# Converter.net
KiCad netlist of a schematic drawn in Altium Designer
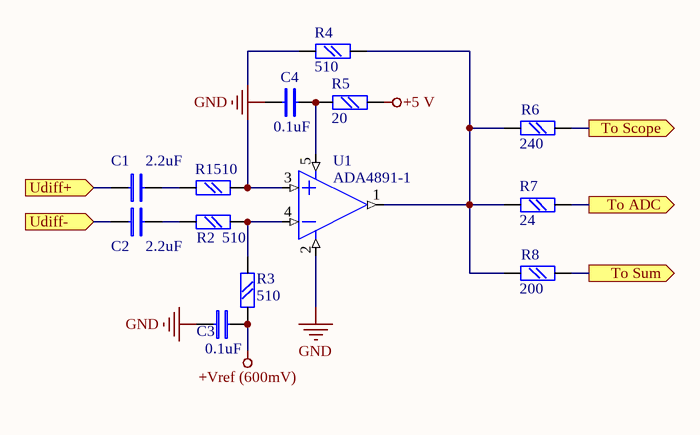
[diagram p0: Converter.SchDoc]

(export (version "E")
  (design (tool "Eeschema 10.0.6"))
  (components
    (comp (ref "C1") (value "2.2uF") (footprint "chip0603") (libsource (lib "vDevice") (part "C")))
    (comp (ref "C2") (value "2.2uF") (footprint "chip0603") (libsource (lib "vDevice") (part "C")))
    (comp (ref "C3") (value "0.1uF") (footprint "chip0603") (libsource (lib "vDevice") (part "C")))
    (comp (ref "C4") (value "0.1uF") (footprint "chip0603") (libsource (lib "vDevice") (part "C")))
    (comp (ref "R1") (value "510") (footprint "chip0603") (libsource (lib "vDevice") (part "R")))
    (comp (ref "R2") (value "510") (footprint "chip0603") (libsource (lib "vDevice") (part "R")))
    (comp (ref "R3") (value "510") (footprint "chip0603") (libsource (lib "vDevice") (part "R")))
    (comp (ref "R4") (value "510") (footprint "chip0603") (libsource (lib "vDevice") (part "R")))
    (comp (ref "R5") (value "20") (footprint "chip0603") (libsource (lib "vDevice") (part "R")))
    (comp (ref "R6") (value "240") (footprint "chip0603") (libsource (lib "vDevice") (part "R")))
    (comp (ref "R7") (value "24") (footprint "chip0603") (libsource (lib "vDevice") (part "R")))
    (comp (ref "R8") (value "200") (footprint "chip0603") (libsource (lib "vDevice") (part "R")))
    (comp (ref "U1") (value "ADA4891-1") (footprint "SOT23-5") (libsource (lib "vAnalog") (part "AD8005ART")))
  )
  (nets
    (net (code "1") (name "+5 V") (class "Default")
      (node (ref "R5") (pin "1") (pinfunction "1_1") (pintype "passive"))
    )
    (net (code "2") (name "+Vref (600mV)") (class "Default")
      (node (ref "C3") (pin "2") (pinfunction "2_2") (pintype "passive"))
      (node (ref "R3") (pin "2") (pinfunction "2_2") (pintype "passive"))
    )
    (net (code "3") (name "/To ADC") (class "Default")
      (node (ref "R7") (pin "2") (pinfunction "2_2") (pintype "passive"))
    )
    (net (code "4") (name "/To Scope") (class "Default")
      (node (ref "R6") (pin "2") (pinfunction "2_2") (pintype "passive"))
    )
    (net (code "5") (name "/To Sum") (class "Default")
      (node (ref "R8") (pin "2") (pinfunction "2_2") (pintype "passive"))
    )
    (net (code "6") (name "/Udiff+") (class "Default")
      (node (ref "C1") (pin "1") (pinfunction "1_1") (pintype "passive"))
    )
    (net (code "7") (name "/Udiff-") (class "Default")
      (node (ref "C2") (pin "1") (pinfunction "1_1") (pintype "passive"))
    )
    (net (code "8") (name "GND") (class "Default")
      (node (ref "C3") (pin "1") (pinfunction "1_1") (pintype "passive"))
      (node (ref "C4") (pin "1") (pinfunction "1_1") (pintype "passive"))
      (node (ref "U1") (pin "2") (pinfunction "E-_2") (pintype "input"))
    )
    (net (code "9") (name "Net-(C1-Pad2)") (class "Default")
      (node (ref "C1") (pin "2") (pinfunction "2_2") (pintype "passive"))
      (node (ref "R1") (pin "1") (pinfunction "1_1") (pintype "passive"))
    )
    (net (code "10") (name "Net-(C2-Pad2)") (class "Default")
      (node (ref "C2") (pin "2") (pinfunction "2_2") (pintype "passive"))
      (node (ref "R2") (pin "1") (pinfunction "1_1") (pintype "passive"))
    )
    (net (code "11") (name "Net-(U1-+IN)") (class "Default")
      (node (ref "R1") (pin "2") (pinfunction "2_2") (pintype "passive"))
      (node (ref "R4") (pin "1") (pinfunction "1_1") (pintype "passive"))
      (node (ref "U1") (pin "3") (pinfunction "+IN_3") (pintype "input"))
    )
    (net (code "12") (name "Net-(U1--IN)") (class "Default")
      (node (ref "R2") (pin "2") (pinfunction "2_2") (pintype "passive"))
      (node (ref "R3") (pin "1") (pinfunction "1_1") (pintype "passive"))
      (node (ref "U1") (pin "4") (pinfunction "-IN_4") (pintype "input"))
    )
    (net (code "13") (name "Net-(U1-E+)") (class "Default")
      (node (ref "C4") (pin "2") (pinfunction "2_2") (pintype "passive"))
      (node (ref "R5") (pin "2") (pinfunction "2_2") (pintype "passive"))
      (node (ref "U1") (pin "5") (pinfunction "E+_5") (pintype "input"))
    )
    (net (code "14") (name "Net-(U1-OUT)") (class "Default")
      (node (ref "R4") (pin "2") (pinfunction "2_2") (pintype "passive"))
      (node (ref "R6") (pin "1") (pinfunction "1_1") (pintype "passive"))
      (node (ref "R7") (pin "1") (pinfunction "1_1") (pintype "passive"))
      (node (ref "R8") (pin "1") (pinfunction "1_1") (pintype "passive"))
      (node (ref "U1") (pin "1") (pinfunction "OUT_1") (pintype "output"))
    )
  )
)
